# Nakaya_Schematic4-handrouting.net
KiCad netlist of a schematic drawn in EAGLE
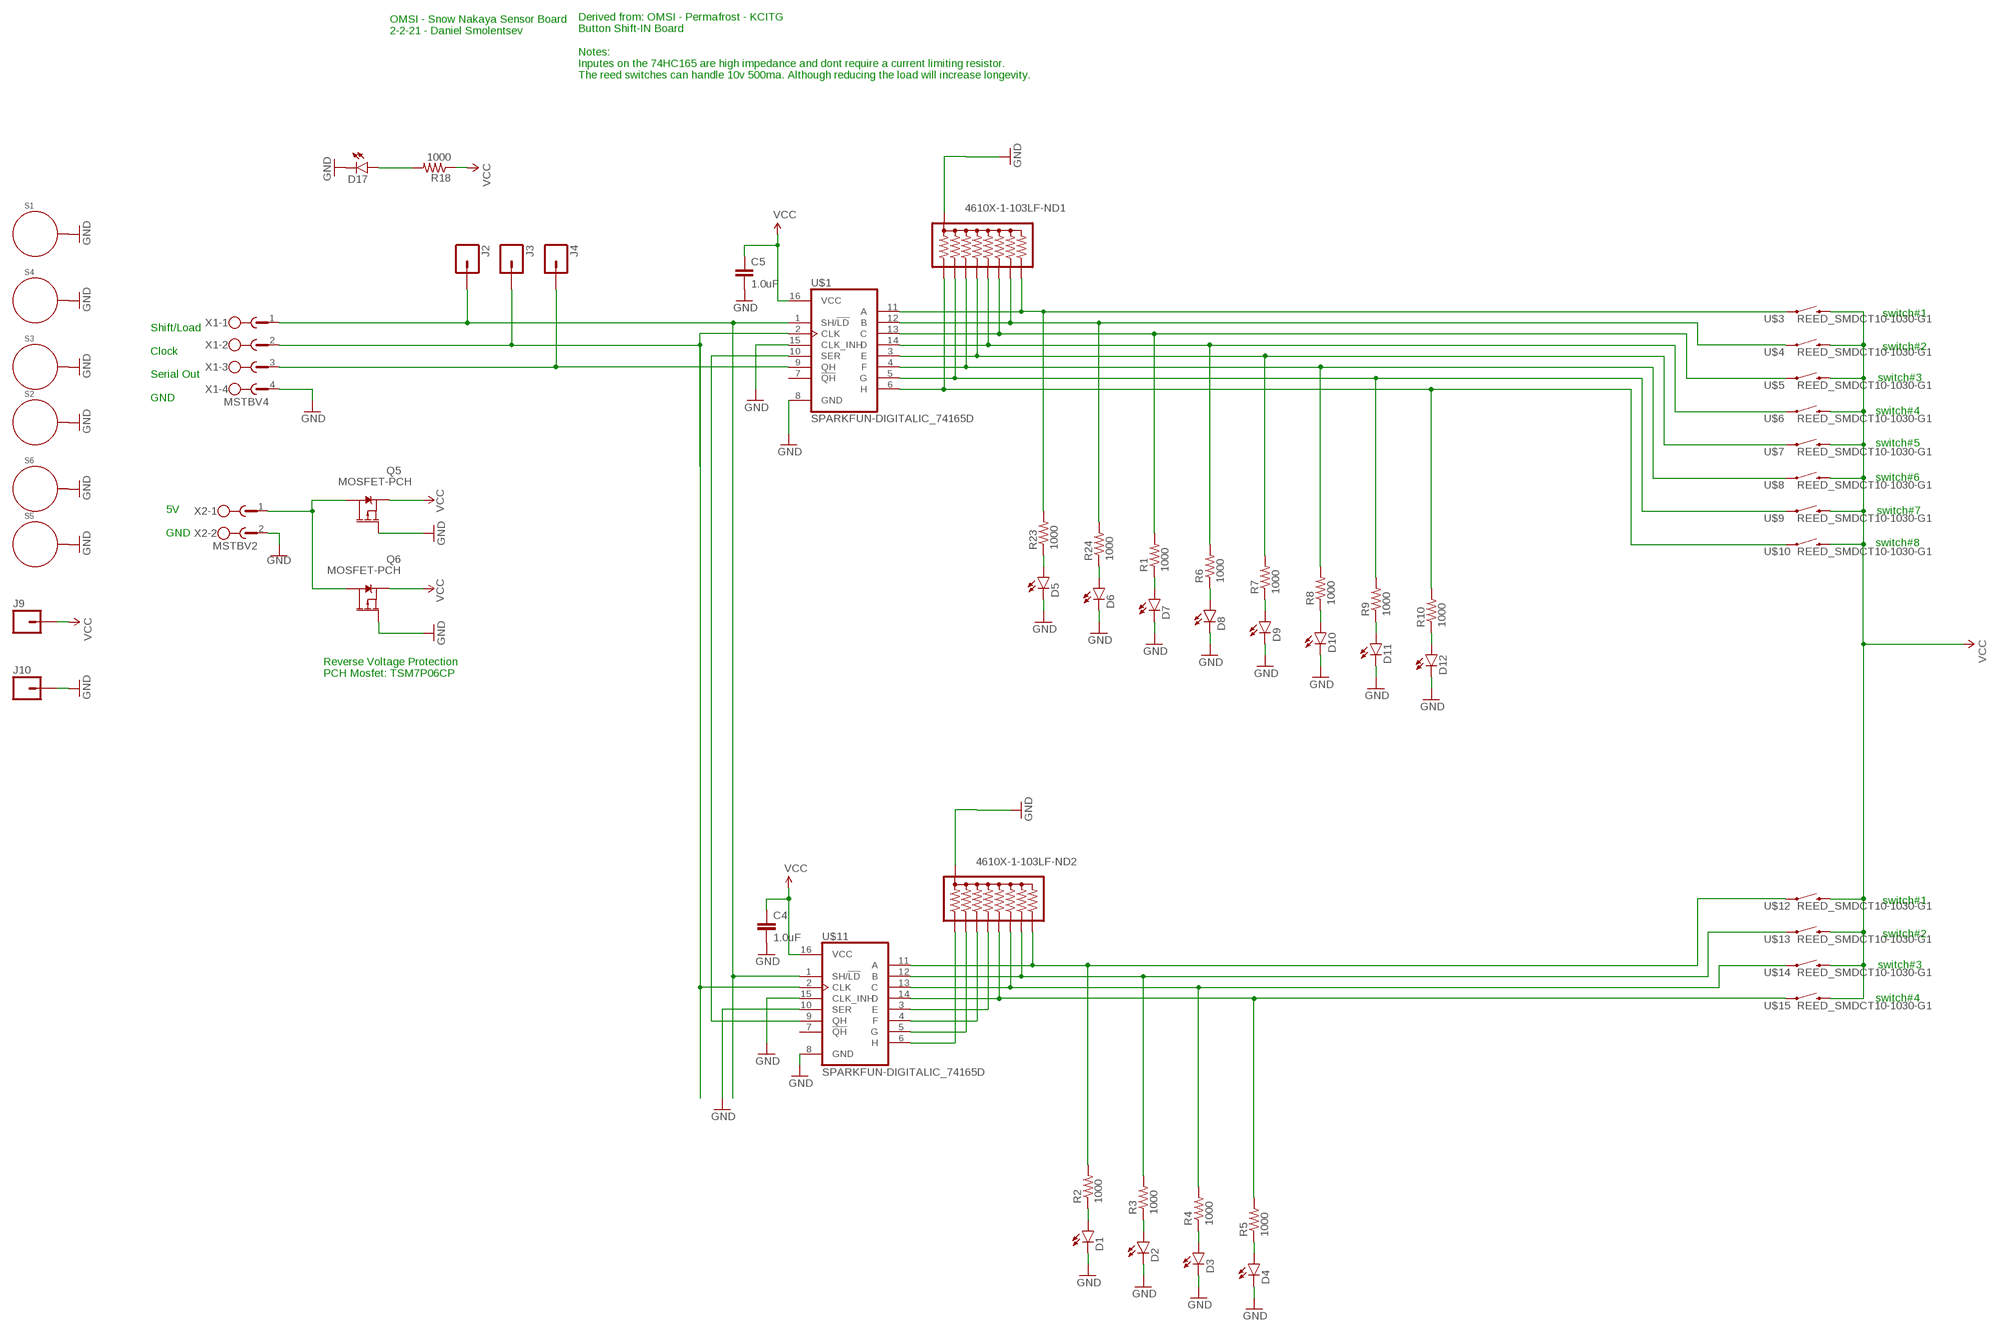
[diagram p0: schematic, sheet 1]

(export (version "E")
  (design (tool "Eeschema 10.0.6"))
  (components
    (comp (ref "4610X-1-103LF-ND1")
      (value "RPACK-BUSSED-8-SIP-PTH-8")
      (footprint "eagle-import:RPACK-SIP-PTH-8")
      (libsource (lib "eagle-import") (part "RPACK-BUSSED-8-SIP-PTH-8"))
    )
    (comp (ref "4610X-1-103LF-ND2")
      (value "RPACK-BUSSED-8-SIP-PTH-8")
      (footprint "eagle-import:RPACK-SIP-PTH-8")
      (libsource (lib "eagle-import") (part "RPACK-BUSSED-8-SIP-PTH-8"))
    )
    (comp (ref "C4")
      (value "1.0uF")
      (footprint "eagle-import:SPARKFUN-CAPACITORS_0805")
      (libsource (lib "eagle-import") (part "SPARKFUN-CAPACITORS_1.0UF-0805-25V-10%"))
    )
    (comp (ref "C5")
      (value "1.0uF")
      (footprint "eagle-import:SPARKFUN-CAPACITORS_0805")
      (libsource (lib "eagle-import") (part "SPARKFUN-CAPACITORS_1.0UF-0805-25V-10%"))
    )
    (comp (ref "D1")
      (value "SPARKFUN-LED_LED1206")
      (footprint "eagle-import:SPARKFUN-LED_LED-1206")
      (libsource (lib "eagle-import") (part "SPARKFUN-LED_LED1206"))
    )
    (comp (ref "D2")
      (value "SPARKFUN-LED_LED1206")
      (footprint "eagle-import:SPARKFUN-LED_LED-1206")
      (libsource (lib "eagle-import") (part "SPARKFUN-LED_LED1206"))
    )
    (comp (ref "D3")
      (value "SPARKFUN-LED_LED1206")
      (footprint "eagle-import:SPARKFUN-LED_LED-1206")
      (libsource (lib "eagle-import") (part "SPARKFUN-LED_LED1206"))
    )
    (comp (ref "D4")
      (value "SPARKFUN-LED_LED1206")
      (footprint "eagle-import:SPARKFUN-LED_LED-1206")
      (libsource (lib "eagle-import") (part "SPARKFUN-LED_LED1206"))
    )
    (comp (ref "D5")
      (value "SPARKFUN-LED_LED1206")
      (footprint "eagle-import:SPARKFUN-LED_LED-1206")
      (libsource (lib "eagle-import") (part "SPARKFUN-LED_LED1206"))
    )
    (comp (ref "D6")
      (value "SPARKFUN-LED_LED1206")
      (footprint "eagle-import:SPARKFUN-LED_LED-1206")
      (libsource (lib "eagle-import") (part "SPARKFUN-LED_LED1206"))
    )
    (comp (ref "D7")
      (value "SPARKFUN-LED_LED1206")
      (footprint "eagle-import:SPARKFUN-LED_LED-1206")
      (libsource (lib "eagle-import") (part "SPARKFUN-LED_LED1206"))
    )
    (comp (ref "D8")
      (value "SPARKFUN-LED_LED1206")
      (footprint "eagle-import:SPARKFUN-LED_LED-1206")
      (libsource (lib "eagle-import") (part "SPARKFUN-LED_LED1206"))
    )
    (comp (ref "D9")
      (value "SPARKFUN-LED_LED1206")
      (footprint "eagle-import:SPARKFUN-LED_LED-1206")
      (libsource (lib "eagle-import") (part "SPARKFUN-LED_LED1206"))
    )
    (comp (ref "D10")
      (value "SPARKFUN-LED_LED1206")
      (footprint "eagle-import:SPARKFUN-LED_LED-1206")
      (libsource (lib "eagle-import") (part "SPARKFUN-LED_LED1206"))
    )
    (comp (ref "D11")
      (value "SPARKFUN-LED_LED1206")
      (footprint "eagle-import:SPARKFUN-LED_LED-1206")
      (libsource (lib "eagle-import") (part "SPARKFUN-LED_LED1206"))
    )
    (comp (ref "D12")
      (value "SPARKFUN-LED_LED1206")
      (footprint "eagle-import:SPARKFUN-LED_LED-1206")
      (libsource (lib "eagle-import") (part "SPARKFUN-LED_LED1206"))
    )
    (comp (ref "D17")
      (value "SPARKFUN-LED_LED1206")
      (footprint "eagle-import:SPARKFUN-LED_LED-1206")
      (libsource (lib "eagle-import") (part "SPARKFUN-LED_LED1206"))
    )
    (comp (ref "J2")
      (value "SPARKFUN-CONNECTORS_M01PTH_NO_SILK_YES_STOP")
      (footprint "eagle-import:SPARKFUN-CONNECTORS_1X01_NO_SILK")
      (libsource (lib "eagle-import") (part "SPARKFUN-CONNECTORS_M01PTH_NO_SILK_YES_STOP"))
    )
    (comp (ref "J3")
      (value "SPARKFUN-CONNECTORS_M01PTH_NO_SILK_YES_STOP")
      (footprint "eagle-import:SPARKFUN-CONNECTORS_1X01_NO_SILK")
      (libsource (lib "eagle-import") (part "SPARKFUN-CONNECTORS_M01PTH_NO_SILK_YES_STOP"))
    )
    (comp (ref "J4")
      (value "SPARKFUN-CONNECTORS_M01PTH_NO_SILK_YES_STOP")
      (footprint "eagle-import:SPARKFUN-CONNECTORS_1X01_NO_SILK")
      (libsource (lib "eagle-import") (part "SPARKFUN-CONNECTORS_M01PTH_NO_SILK_YES_STOP"))
    )
    (comp (ref "J9")
      (value "SPARKFUN-CONNECTORS_M01PTH_NO_SILK_YES_STOP")
      (footprint "eagle-import:SPARKFUN-CONNECTORS_1X01_NO_SILK")
      (libsource (lib "eagle-import") (part "SPARKFUN-CONNECTORS_M01PTH_NO_SILK_YES_STOP"))
    )
    (comp (ref "J10")
      (value "SPARKFUN-CONNECTORS_M01PTH_NO_SILK_YES_STOP")
      (footprint "eagle-import:SPARKFUN-CONNECTORS_1X01_NO_SILK")
      (libsource (lib "eagle-import") (part "SPARKFUN-CONNECTORS_M01PTH_NO_SILK_YES_STOP"))
    )
    (comp (ref "Q5")
      (value "MOSFET-PCH")
      (footprint "eagle-import:DPAK")
      (libsource (lib "eagle-import") (part "MOSFET-PCH"))
    )
    (comp (ref "Q6")
      (value "MOSFET-PCH")
      (footprint "eagle-import:DPAK")
      (libsource (lib "eagle-import") (part "MOSFET-PCH"))
    )
    (comp (ref "R1")
      (value "1000")
      (footprint "eagle-import:SPARKFUN-PASSIVES_0805_1")
      (libsource (lib "eagle-import") (part "SPARKFUN-PASSIVES_RESISTOR0805-RES"))
    )
    (comp (ref "R2")
      (value "1000")
      (footprint "eagle-import:SPARKFUN-PASSIVES_0805_1")
      (libsource (lib "eagle-import") (part "SPARKFUN-PASSIVES_RESISTOR0805-RES"))
    )
    (comp (ref "R3")
      (value "1000")
      (footprint "eagle-import:SPARKFUN-PASSIVES_0805_1")
      (libsource (lib "eagle-import") (part "SPARKFUN-PASSIVES_RESISTOR0805-RES"))
    )
    (comp (ref "R4")
      (value "1000")
      (footprint "eagle-import:SPARKFUN-PASSIVES_0805_1")
      (libsource (lib "eagle-import") (part "SPARKFUN-PASSIVES_RESISTOR0805-RES"))
    )
    (comp (ref "R5")
      (value "1000")
      (footprint "eagle-import:SPARKFUN-PASSIVES_0805_1")
      (libsource (lib "eagle-import") (part "SPARKFUN-PASSIVES_RESISTOR0805-RES"))
    )
    (comp (ref "R6")
      (value "1000")
      (footprint "eagle-import:SPARKFUN-PASSIVES_0805_1")
      (libsource (lib "eagle-import") (part "SPARKFUN-PASSIVES_RESISTOR0805-RES"))
    )
    (comp (ref "R7")
      (value "1000")
      (footprint "eagle-import:SPARKFUN-PASSIVES_0805_1")
      (libsource (lib "eagle-import") (part "SPARKFUN-PASSIVES_RESISTOR0805-RES"))
    )
    (comp (ref "R8")
      (value "1000")
      (footprint "eagle-import:SPARKFUN-PASSIVES_0805_1")
      (libsource (lib "eagle-import") (part "SPARKFUN-PASSIVES_RESISTOR0805-RES"))
    )
    (comp (ref "R9")
      (value "1000")
      (footprint "eagle-import:SPARKFUN-PASSIVES_0805_1")
      (libsource (lib "eagle-import") (part "SPARKFUN-PASSIVES_RESISTOR0805-RES"))
    )
    (comp (ref "R10")
      (value "1000")
      (footprint "eagle-import:SPARKFUN-PASSIVES_0805_1")
      (libsource (lib "eagle-import") (part "SPARKFUN-PASSIVES_RESISTOR0805-RES"))
    )
    (comp (ref "R18")
      (value "1000")
      (footprint "eagle-import:SPARKFUN-PASSIVES_0805_1")
      (libsource (lib "eagle-import") (part "SPARKFUN-PASSIVES_RESISTOR0805-RES"))
    )
    (comp (ref "R23")
      (value "1000")
      (footprint "eagle-import:SPARKFUN-PASSIVES_0805_1")
      (libsource (lib "eagle-import") (part "SPARKFUN-PASSIVES_RESISTOR0805-RES"))
    )
    (comp (ref "R24")
      (value "1000")
      (footprint "eagle-import:SPARKFUN-PASSIVES_0805_1")
      (libsource (lib "eagle-import") (part "SPARKFUN-PASSIVES_RESISTOR0805-RES"))
    )
    (comp (ref "S1")
      (value "STANDOFF_ELECTRICAL.18\"")
      (footprint "eagle-import:STANDOFF_ELECTRIC_#8_OVERSIZED")
      (libsource (lib "eagle-import") (part "STANDOFF_ELECTRICAL.18{dblquote}"))
    )
    (comp (ref "S2")
      (value "STANDOFF_ELECTRICAL.18\"")
      (footprint "eagle-import:STANDOFF_ELECTRIC_#8_OVERSIZED")
      (libsource (lib "eagle-import") (part "STANDOFF_ELECTRICAL.18{dblquote}"))
    )
    (comp (ref "S3")
      (value "STANDOFF_ELECTRICAL.18\"")
      (footprint "eagle-import:STANDOFF_ELECTRIC_#8_OVERSIZED")
      (libsource (lib "eagle-import") (part "STANDOFF_ELECTRICAL.18{dblquote}"))
    )
    (comp (ref "S4")
      (value "STANDOFF_ELECTRICAL.18\"")
      (footprint "eagle-import:STANDOFF_ELECTRIC_#8_OVERSIZED")
      (libsource (lib "eagle-import") (part "STANDOFF_ELECTRICAL.18{dblquote}"))
    )
    (comp (ref "S5")
      (value "STANDOFF_ELECTRICAL.18\"")
      (footprint "eagle-import:STANDOFF_ELECTRIC_#8_OVERSIZED")
      (libsource (lib "eagle-import") (part "STANDOFF_ELECTRICAL.18{dblquote}"))
    )
    (comp (ref "S6")
      (value "STANDOFF_ELECTRICAL.18\"")
      (footprint "eagle-import:STANDOFF_ELECTRIC_#8_OVERSIZED")
      (libsource (lib "eagle-import") (part "STANDOFF_ELECTRICAL.18{dblquote}"))
    )
    (comp (ref "U$1")
      (value "SPARKFUN-DIGITALIC_74165D")
      (footprint "eagle-import:SPARKFUN-DIGITALIC_SO16")
      (libsource (lib "eagle-import") (part "SPARKFUN-DIGITALIC_74165D"))
    )
    (comp (ref "U$3")
      (value "REED_SMDCT10-1030-G1")
      (footprint "eagle-import:REED_SMD_2")
      (libsource (lib "eagle-import") (part "REED_SMDCT10-1030-G1"))
    )
    (comp (ref "U$4")
      (value "REED_SMDCT10-1030-G1")
      (footprint "eagle-import:REED_SMD_2")
      (libsource (lib "eagle-import") (part "REED_SMDCT10-1030-G1"))
    )
    (comp (ref "U$5")
      (value "REED_SMDCT10-1030-G1")
      (footprint "eagle-import:REED_SMD_2")
      (libsource (lib "eagle-import") (part "REED_SMDCT10-1030-G1"))
    )
    (comp (ref "U$6")
      (value "REED_SMDCT10-1030-G1")
      (footprint "eagle-import:REED_SMD_2")
      (libsource (lib "eagle-import") (part "REED_SMDCT10-1030-G1"))
    )
    (comp (ref "U$7")
      (value "REED_SMDCT10-1030-G1")
      (footprint "eagle-import:REED_SMD_2")
      (libsource (lib "eagle-import") (part "REED_SMDCT10-1030-G1"))
    )
    (comp (ref "U$8")
      (value "REED_SMDCT10-1030-G1")
      (footprint "eagle-import:REED_SMD_2")
      (libsource (lib "eagle-import") (part "REED_SMDCT10-1030-G1"))
    )
    (comp (ref "U$9")
      (value "REED_SMDCT10-1030-G1")
      (footprint "eagle-import:REED_SMD_2")
      (libsource (lib "eagle-import") (part "REED_SMDCT10-1030-G1"))
    )
    (comp (ref "U$10")
      (value "REED_SMDCT10-1030-G1")
      (footprint "eagle-import:REED_SMD_2")
      (libsource (lib "eagle-import") (part "REED_SMDCT10-1030-G1"))
    )
    (comp (ref "U$11")
      (value "SPARKFUN-DIGITALIC_74165D")
      (footprint "eagle-import:SPARKFUN-DIGITALIC_SO16")
      (libsource (lib "eagle-import") (part "SPARKFUN-DIGITALIC_74165D"))
    )
    (comp (ref "U$12")
      (value "REED_SMDCT10-1030-G1")
      (footprint "eagle-import:REED_SMD_2")
      (libsource (lib "eagle-import") (part "REED_SMDCT10-1030-G1"))
    )
    (comp (ref "U$13")
      (value "REED_SMDCT10-1030-G1")
      (footprint "eagle-import:REED_SMD_2")
      (libsource (lib "eagle-import") (part "REED_SMDCT10-1030-G1"))
    )
    (comp (ref "U$14")
      (value "REED_SMDCT10-1030-G1")
      (footprint "eagle-import:REED_SMD_2")
      (libsource (lib "eagle-import") (part "REED_SMDCT10-1030-G1"))
    )
    (comp (ref "U$15")
      (value "REED_SMDCT10-1030-G1")
      (footprint "eagle-import:REED_SMD_2")
      (libsource (lib "eagle-import") (part "REED_SMDCT10-1030-G1"))
    )
    (comp (ref "X1")
      (value "MSTBV4")
      (footprint "eagle-import:MSTBV4")
      (fields (field (name "MPN") "MSTBV 2,5/4-GF-5.08"))
      (libsource (lib "eagle-import") (part "MSTBV4"))
    )
    (comp (ref "X2")
      (value "MSTBV2")
      (footprint "eagle-import:MSTBV2")
      (fields (field (name "MPN") "MSTBV 2,5/2-GF-5.08"))
      (libsource (lib "eagle-import") (part "MSTBV2"))
    )
  )
  (nets
    (net (code "1") (name "GND") (class "Default")
      (node (ref "4610X-1-103LF-ND1") (pin "P$1") (pinfunction "1_P$1") (pintype "passive"))
      (node (ref "4610X-1-103LF-ND2") (pin "P$1") (pinfunction "1_P$1") (pintype "passive"))
      (node (ref "C4") (pin "2") (pinfunction "2_2") (pintype "passive"))
      (node (ref "C5") (pin "2") (pinfunction "2_2") (pintype "passive"))
      (node (ref "D1") (pin "C") (pinfunction "C_C") (pintype "passive"))
      (node (ref "D10") (pin "C") (pinfunction "C_C") (pintype "passive"))
      (node (ref "D11") (pin "C") (pinfunction "C_C") (pintype "passive"))
      (node (ref "D12") (pin "C") (pinfunction "C_C") (pintype "passive"))
      (node (ref "D17") (pin "C") (pinfunction "C_C") (pintype "passive"))
      (node (ref "D2") (pin "C") (pinfunction "C_C") (pintype "passive"))
      (node (ref "D3") (pin "C") (pinfunction "C_C") (pintype "passive"))
      (node (ref "D4") (pin "C") (pinfunction "C_C") (pintype "passive"))
      (node (ref "D5") (pin "C") (pinfunction "C_C") (pintype "passive"))
      (node (ref "D6") (pin "C") (pinfunction "C_C") (pintype "passive"))
      (node (ref "D7") (pin "C") (pinfunction "C_C") (pintype "passive"))
      (node (ref "D8") (pin "C") (pinfunction "C_C") (pintype "passive"))
      (node (ref "D9") (pin "C") (pinfunction "C_C") (pintype "passive"))
      (node (ref "J10") (pin "1") (pinfunction "1_1") (pintype "passive"))
      (node (ref "Q5") (pin "1") (pinfunction "G_1") (pintype "bidirectional"))
      (node (ref "Q6") (pin "1") (pinfunction "G_1") (pintype "bidirectional"))
      (node (ref "S1") (pin "P$1") (pinfunction "P$1_P$1") (pintype "bidirectional"))
      (node (ref "S2") (pin "P$1") (pinfunction "P$1_P$1") (pintype "bidirectional"))
      (node (ref "S3") (pin "P$1") (pinfunction "P$1_P$1") (pintype "bidirectional"))
      (node (ref "S4") (pin "P$1") (pinfunction "P$1_P$1") (pintype "bidirectional"))
      (node (ref "S5") (pin "P$1") (pinfunction "P$1_P$1") (pintype "bidirectional"))
      (node (ref "S6") (pin "P$1") (pinfunction "P$1_P$1") (pintype "bidirectional"))
      (node (ref "U$1") (pin "15") (pinfunction "CLK_INH_15") (pintype "input"))
      (node (ref "U$1") (pin "8") (pinfunction "GND_8") (pintype "power_in"))
      (node (ref "U$11") (pin "10") (pinfunction "SER_10") (pintype "input"))
      (node (ref "U$11") (pin "15") (pinfunction "CLK_INH_15") (pintype "input"))
      (node (ref "U$11") (pin "8") (pinfunction "GND_8") (pintype "power_in"))
      (node (ref "X1") (pin "4") (pinfunction "1_4") (pintype "passive"))
      (node (ref "X2") (pin "2") (pinfunction "1_2") (pintype "passive"))
    )
    (net (code "2") (name "Net-(4610X-1-103LF-ND1-2)") (class "Default")
      (node (ref "4610X-1-103LF-ND1") (pin "P$2") (pinfunction "2_P$2") (pintype "passive"))
      (node (ref "R10") (pin "2") (pinfunction "2_2") (pintype "passive"))
      (node (ref "U$1") (pin "6") (pinfunction "H_6") (pintype "tri_state"))
      (node (ref "U$10") (pin "3") (pinfunction "1_3") (pintype "passive"))
    )
    (net (code "3") (name "Net-(4610X-1-103LF-ND1-3)") (class "Default")
      (node (ref "4610X-1-103LF-ND1") (pin "P$3") (pinfunction "3_P$3") (pintype "passive"))
      (node (ref "R9") (pin "2") (pinfunction "2_2") (pintype "passive"))
      (node (ref "U$1") (pin "5") (pinfunction "G_5") (pintype "tri_state"))
      (node (ref "U$9") (pin "3") (pinfunction "1_3") (pintype "passive"))
    )
    (net (code "4") (name "Net-(4610X-1-103LF-ND1-4)") (class "Default")
      (node (ref "4610X-1-103LF-ND1") (pin "P$4") (pinfunction "4_P$4") (pintype "passive"))
      (node (ref "R8") (pin "2") (pinfunction "2_2") (pintype "passive"))
      (node (ref "U$1") (pin "4") (pinfunction "F_4") (pintype "tri_state"))
      (node (ref "U$8") (pin "3") (pinfunction "1_3") (pintype "passive"))
    )
    (net (code "5") (name "Net-(4610X-1-103LF-ND1-5)") (class "Default")
      (node (ref "4610X-1-103LF-ND1") (pin "P$5") (pinfunction "5_P$5") (pintype "passive"))
      (node (ref "R7") (pin "2") (pinfunction "2_2") (pintype "passive"))
      (node (ref "U$1") (pin "3") (pinfunction "E_3") (pintype "tri_state"))
      (node (ref "U$7") (pin "3") (pinfunction "1_3") (pintype "passive"))
    )
    (net (code "6") (name "Net-(4610X-1-103LF-ND1-6)") (class "Default")
      (node (ref "4610X-1-103LF-ND1") (pin "P$6") (pinfunction "6_P$6") (pintype "passive"))
      (node (ref "R6") (pin "2") (pinfunction "2_2") (pintype "passive"))
      (node (ref "U$1") (pin "14") (pinfunction "D_14") (pintype "tri_state"))
      (node (ref "U$6") (pin "3") (pinfunction "1_3") (pintype "passive"))
    )
    (net (code "7") (name "Net-(4610X-1-103LF-ND1-7)") (class "Default")
      (node (ref "4610X-1-103LF-ND1") (pin "P$7") (pinfunction "7_P$7") (pintype "passive"))
      (node (ref "R1") (pin "2") (pinfunction "2_2") (pintype "passive"))
      (node (ref "U$1") (pin "13") (pinfunction "C_13") (pintype "tri_state"))
      (node (ref "U$5") (pin "3") (pinfunction "1_3") (pintype "passive"))
    )
    (net (code "8") (name "Net-(4610X-1-103LF-ND1-8)") (class "Default")
      (node (ref "4610X-1-103LF-ND1") (pin "P$8") (pinfunction "8_P$8") (pintype "passive"))
      (node (ref "R24") (pin "2") (pinfunction "2_2") (pintype "passive"))
      (node (ref "U$1") (pin "12") (pinfunction "B_12") (pintype "tri_state"))
      (node (ref "U$4") (pin "3") (pinfunction "1_3") (pintype "passive"))
    )
    (net (code "9") (name "Net-(4610X-1-103LF-ND1-9)") (class "Default")
      (node (ref "4610X-1-103LF-ND1") (pin "P$9") (pinfunction "9_P$9") (pintype "passive"))
      (node (ref "R23") (pin "2") (pinfunction "2_2") (pintype "passive"))
      (node (ref "U$1") (pin "11") (pinfunction "A_11") (pintype "tri_state"))
      (node (ref "U$3") (pin "3") (pinfunction "1_3") (pintype "passive"))
    )
    (net (code "10") (name "Net-(4610X-1-103LF-ND2-2)") (class "Default")
      (node (ref "4610X-1-103LF-ND2") (pin "P$2") (pinfunction "2_P$2") (pintype "passive"))
      (node (ref "U$11") (pin "6") (pinfunction "H_6") (pintype "tri_state"))
    )
    (net (code "11") (name "Net-(4610X-1-103LF-ND2-3)") (class "Default")
      (node (ref "4610X-1-103LF-ND2") (pin "P$3") (pinfunction "3_P$3") (pintype "passive"))
      (node (ref "U$11") (pin "5") (pinfunction "G_5") (pintype "tri_state"))
    )
    (net (code "12") (name "Net-(4610X-1-103LF-ND2-4)") (class "Default")
      (node (ref "4610X-1-103LF-ND2") (pin "P$4") (pinfunction "4_P$4") (pintype "passive"))
      (node (ref "U$11") (pin "4") (pinfunction "F_4") (pintype "tri_state"))
    )
    (net (code "13") (name "Net-(4610X-1-103LF-ND2-5)") (class "Default")
      (node (ref "4610X-1-103LF-ND2") (pin "P$5") (pinfunction "5_P$5") (pintype "passive"))
      (node (ref "U$11") (pin "3") (pinfunction "E_3") (pintype "tri_state"))
    )
    (net (code "14") (name "Net-(4610X-1-103LF-ND2-6)") (class "Default")
      (node (ref "4610X-1-103LF-ND2") (pin "P$6") (pinfunction "6_P$6") (pintype "passive"))
      (node (ref "R5") (pin "2") (pinfunction "2_2") (pintype "passive"))
      (node (ref "U$11") (pin "14") (pinfunction "D_14") (pintype "tri_state"))
      (node (ref "U$15") (pin "3") (pinfunction "1_3") (pintype "passive"))
    )
    (net (code "15") (name "Net-(4610X-1-103LF-ND2-7)") (class "Default")
      (node (ref "4610X-1-103LF-ND2") (pin "P$7") (pinfunction "7_P$7") (pintype "passive"))
      (node (ref "R4") (pin "2") (pinfunction "2_2") (pintype "passive"))
      (node (ref "U$11") (pin "13") (pinfunction "C_13") (pintype "tri_state"))
      (node (ref "U$14") (pin "3") (pinfunction "1_3") (pintype "passive"))
    )
    (net (code "16") (name "Net-(4610X-1-103LF-ND2-8)") (class "Default")
      (node (ref "4610X-1-103LF-ND2") (pin "P$8") (pinfunction "8_P$8") (pintype "passive"))
      (node (ref "R3") (pin "2") (pinfunction "2_2") (pintype "passive"))
      (node (ref "U$11") (pin "12") (pinfunction "B_12") (pintype "tri_state"))
      (node (ref "U$13") (pin "3") (pinfunction "1_3") (pintype "passive"))
    )
    (net (code "17") (name "Net-(4610X-1-103LF-ND2-9)") (class "Default")
      (node (ref "4610X-1-103LF-ND2") (pin "P$9") (pinfunction "9_P$9") (pintype "passive"))
      (node (ref "R2") (pin "2") (pinfunction "2_2") (pintype "passive"))
      (node (ref "U$11") (pin "11") (pinfunction "A_11") (pintype "tri_state"))
      (node (ref "U$12") (pin "3") (pinfunction "1_3") (pintype "passive"))
    )
    (net (code "18") (name "Net-(D1-PadA)") (class "Default")
      (node (ref "D1") (pin "A") (pinfunction "A_A") (pintype "passive"))
      (node (ref "R2") (pin "1") (pinfunction "1_1") (pintype "passive"))
    )
    (net (code "19") (name "Net-(D2-PadA)") (class "Default")
      (node (ref "D2") (pin "A") (pinfunction "A_A") (pintype "passive"))
      (node (ref "R3") (pin "1") (pinfunction "1_1") (pintype "passive"))
    )
    (net (code "20") (name "Net-(D3-PadA)") (class "Default")
      (node (ref "D3") (pin "A") (pinfunction "A_A") (pintype "passive"))
      (node (ref "R4") (pin "1") (pinfunction "1_1") (pintype "passive"))
    )
    (net (code "21") (name "Net-(D4-PadA)") (class "Default")
      (node (ref "D4") (pin "A") (pinfunction "A_A") (pintype "passive"))
      (node (ref "R5") (pin "1") (pinfunction "1_1") (pintype "passive"))
    )
    (net (code "22") (name "Net-(D5-PadA)") (class "Default")
      (node (ref "D5") (pin "A") (pinfunction "A_A") (pintype "passive"))
      (node (ref "R23") (pin "1") (pinfunction "1_1") (pintype "passive"))
    )
    (net (code "23") (name "Net-(D6-PadA)") (class "Default")
      (node (ref "D6") (pin "A") (pinfunction "A_A") (pintype "passive"))
      (node (ref "R24") (pin "1") (pinfunction "1_1") (pintype "passive"))
    )
    (net (code "24") (name "Net-(D7-PadA)") (class "Default")
      (node (ref "D7") (pin "A") (pinfunction "A_A") (pintype "passive"))
      (node (ref "R1") (pin "1") (pinfunction "1_1") (pintype "passive"))
    )
    (net (code "25") (name "Net-(D8-PadA)") (class "Default")
      (node (ref "D8") (pin "A") (pinfunction "A_A") (pintype "passive"))
      (node (ref "R6") (pin "1") (pinfunction "1_1") (pintype "passive"))
    )
    (net (code "26") (name "Net-(D9-PadA)") (class "Default")
      (node (ref "D9") (pin "A") (pinfunction "A_A") (pintype "passive"))
      (node (ref "R7") (pin "1") (pinfunction "1_1") (pintype "passive"))
    )
    (net (code "27") (name "Net-(D10-PadA)") (class "Default")
      (node (ref "D10") (pin "A") (pinfunction "A_A") (pintype "passive"))
      (node (ref "R8") (pin "1") (pinfunction "1_1") (pintype "passive"))
    )
    (net (code "28") (name "Net-(D11-PadA)") (class "Default")
      (node (ref "D11") (pin "A") (pinfunction "A_A") (pintype "passive"))
      (node (ref "R9") (pin "1") (pinfunction "1_1") (pintype "passive"))
    )
    (net (code "29") (name "Net-(D12-PadA)") (class "Default")
      (node (ref "D12") (pin "A") (pinfunction "A_A") (pintype "passive"))
      (node (ref "R10") (pin "1") (pinfunction "1_1") (pintype "passive"))
    )
    (net (code "30") (name "Net-(D17-PadA)") (class "Default")
      (node (ref "D17") (pin "A") (pinfunction "A_A") (pintype "passive"))
      (node (ref "R18") (pin "2") (pinfunction "2_2") (pintype "passive"))
    )
    (net (code "31") (name "Net-(Q5-D)") (class "Default")
      (node (ref "Q5") (pin "4") (pinfunction "D_4") (pintype "bidirectional"))
      (node (ref "Q6") (pin "4") (pinfunction "D_4") (pintype "bidirectional"))
      (node (ref "X2") (pin "1") (pinfunction "1_1") (pintype "passive"))
    )
    (net (code "32") (name "Net-(U$1-CLK)") (class "Default")
      (node (ref "J3") (pin "1") (pinfunction "1_1") (pintype "passive"))
      (node (ref "U$1") (pin "2") (pinfunction "CLK_2") (pintype "input"))
      (node (ref "U$11") (pin "2") (pinfunction "CLK_2") (pintype "input"))
      (node (ref "X1") (pin "2") (pinfunction "1_2") (pintype "passive"))
    )
    (net (code "33") (name "Net-(U$1-QH)") (class "Default")
      (node (ref "J4") (pin "1") (pinfunction "1_1") (pintype "passive"))
      (node (ref "U$1") (pin "9") (pinfunction "QH_9") (pintype "tri_state"))
      (node (ref "X1") (pin "3") (pinfunction "1_3") (pintype "passive"))
    )
    (net (code "34") (name "Net-(U$1-SER)") (class "Default")
      (node (ref "U$1") (pin "10") (pinfunction "SER_10") (pintype "input"))
      (node (ref "U$11") (pin "9") (pinfunction "QH_9") (pintype "tri_state"))
    )
    (net (code "35") (name "Net-(U$1-SH{slash}~{LD})") (class "Default")
      (node (ref "J2") (pin "1") (pinfunction "1_1") (pintype "passive"))
      (node (ref "U$1") (pin "1") (pinfunction "SH/~{LD}_1") (pintype "input"))
      (node (ref "U$11") (pin "1") (pinfunction "SH/~{LD}_1") (pintype "input"))
      (node (ref "X1") (pin "1") (pinfunction "1_1") (pintype "passive"))
    )
    (net (code "36") (name "VCC") (class "Default")
      (node (ref "C4") (pin "1") (pinfunction "1_1") (pintype "passive"))
      (node (ref "C5") (pin "1") (pinfunction "1_1") (pintype "passive"))
      (node (ref "J9") (pin "1") (pinfunction "1_1") (pintype "passive"))
      (node (ref "Q5") (pin "3") (pinfunction "S_3") (pintype "bidirectional"))
      (node (ref "Q6") (pin "3") (pinfunction "S_3") (pintype "bidirectional"))
      (node (ref "R18") (pin "1") (pinfunction "1_1") (pintype "passive"))
      (node (ref "U$1") (pin "16") (pinfunction "VCC_16") (pintype "power_in"))
      (node (ref "U$10") (pin "4") (pinfunction "2_4") (pintype "passive"))
      (node (ref "U$11") (pin "16") (pinfunction "VCC_16") (pintype "power_in"))
      (node (ref "U$12") (pin "4") (pinfunction "2_4") (pintype "passive"))
      (node (ref "U$13") (pin "4") (pinfunction "2_4") (pintype "passive"))
      (node (ref "U$14") (pin "4") (pinfunction "2_4") (pintype "passive"))
      (node (ref "U$15") (pin "4") (pinfunction "2_4") (pintype "passive"))
      (node (ref "U$3") (pin "4") (pinfunction "2_4") (pintype "passive"))
      (node (ref "U$4") (pin "4") (pinfunction "2_4") (pintype "passive"))
      (node (ref "U$5") (pin "4") (pinfunction "2_4") (pintype "passive"))
      (node (ref "U$6") (pin "4") (pinfunction "2_4") (pintype "passive"))
      (node (ref "U$7") (pin "4") (pinfunction "2_4") (pintype "passive"))
      (node (ref "U$8") (pin "4") (pinfunction "2_4") (pintype "passive"))
      (node (ref "U$9") (pin "4") (pinfunction "2_4") (pintype "passive"))
    )
    (net (code "37") (name "unconnected-(U$1-~{QH}-Pad7)") (class "Default")
      (node (ref "U$1") (pin "7") (pinfunction "~{QH}_7") (pintype "input"))
    )
    (net (code "38") (name "unconnected-(U$11-~{QH}-Pad7)") (class "Default")
      (node (ref "U$11") (pin "7") (pinfunction "~{QH}_7") (pintype "input"))
    )
  )
)
